# RegisterMemAddr.net
KiCad netlist of a schematic drawn in Altium Designer
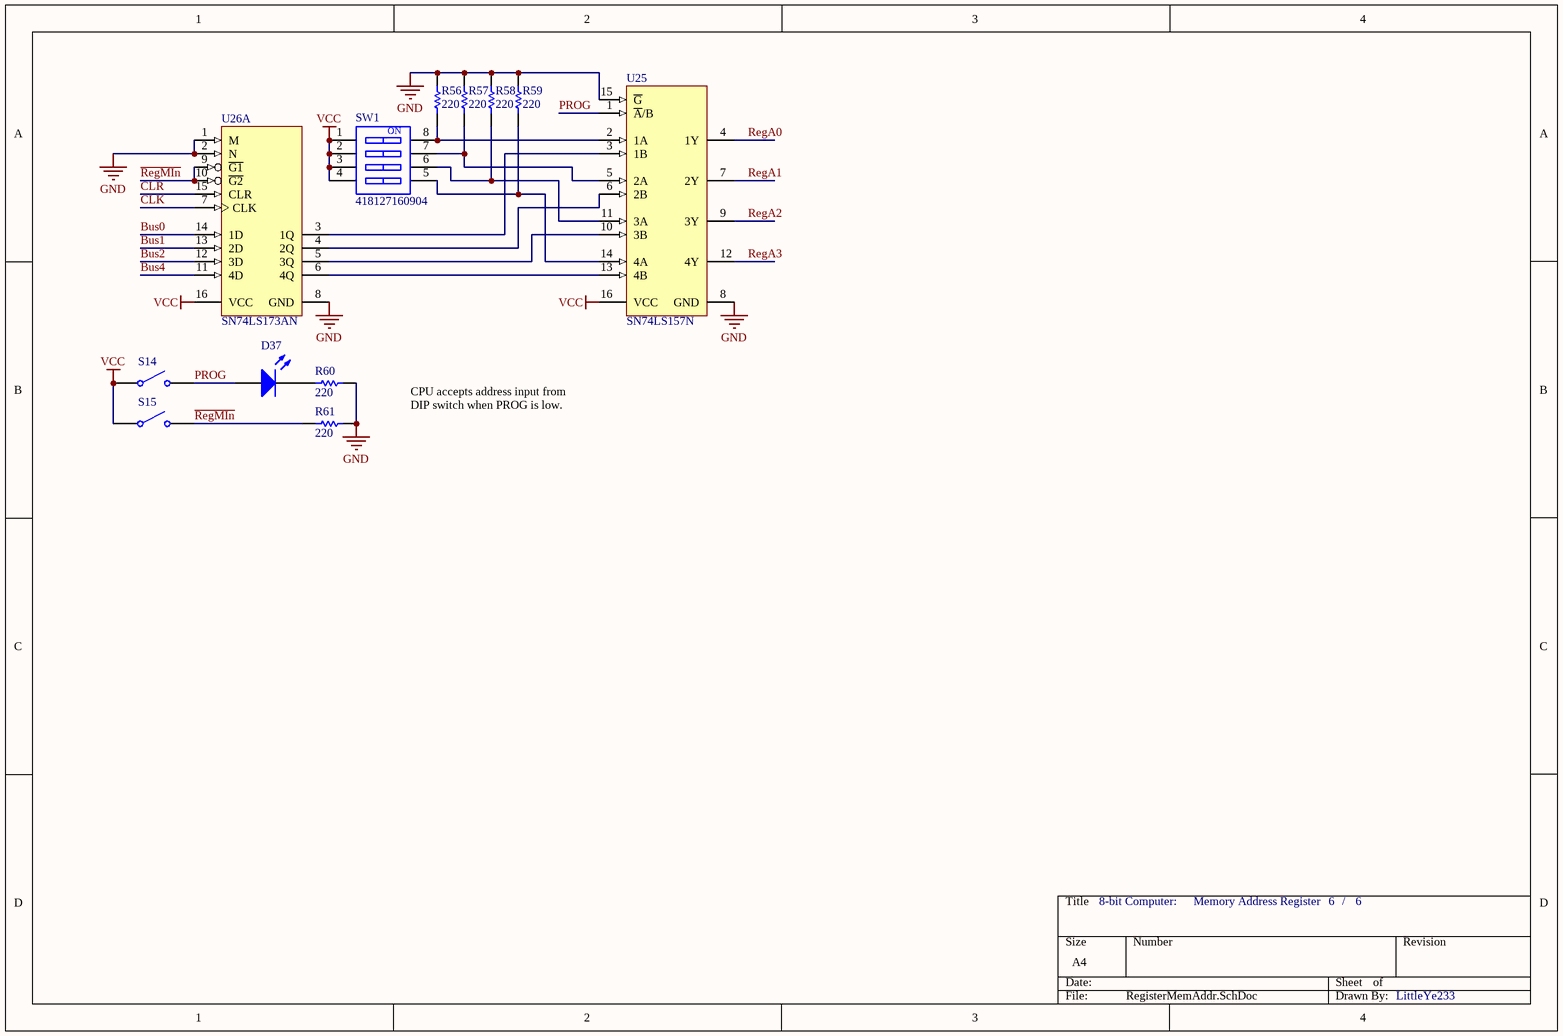
[diagram p0: RegisterMemAddr.SchDoc]

(export (version "E")
  (design (tool "Eeschema 10.0.6"))
  (components
    (comp (ref "D37")
      (value "Light-Emitting Diode")
      (libsource (lib "Simulation Generic Components") (part "LED"))
    )
    (comp (ref "R56")
      (value "220")
      (description "Resistor")
      (libsource (lib "Simulation Generic Components") (part "Resistor"))
    )
    (comp (ref "R57")
      (value "220")
      (description "Resistor")
      (libsource (lib "Simulation Generic Components") (part "Resistor"))
    )
    (comp (ref "R58")
      (value "220")
      (description "Resistor")
      (libsource (lib "Simulation Generic Components") (part "Resistor"))
    )
    (comp (ref "R59")
      (value "220")
      (description "Resistor")
      (libsource (lib "Simulation Generic Components") (part "Resistor"))
    )
    (comp (ref "R60")
      (value "220")
      (description "Resistor")
      (libsource (lib "Simulation Generic Components") (part "Resistor"))
    )
    (comp (ref "R61")
      (value "220")
      (description "Resistor")
      (libsource (lib "Simulation Generic Components") (part "Resistor"))
    )
    (comp (ref "S14")
      (value "Single-Pole, Single-Throw Switch")
      (libsource (lib "Simulation Generic Components") (part "SPST SW"))
    )
    (comp (ref "S15")
      (value "Single-Pole, Single-Throw Switch")
      (libsource (lib "Simulation Generic Components") (part "SPST SW"))
    )
    (comp (ref "SW1")
      (value "418127160904")
      (footprint "418127160904")
      (libsource (lib "418127160904") (part "CMP-1439-00004-2"))
    )
    (comp (ref "U25")
      (value "SN74LS157N")
      (footprint "N0016A")
      (description "Quadruple 2-Line To 1-Line Data Selectors/Multiplexers, N0016A, TUBE")
      (fields
        (field (name "MANUFACTURER") "Texas Instruments")
        (field (name "GENERIC PART NUMBER") "SN74LS157")
      )
      (libsource (lib "SN74LS157N") (part "CMP-1633-00683-2"))
    )
    (comp (ref "U26")
      (value "SN74LS173AN")
      (footprint "N0016A")
      (description "4-Bit D-type Registers with 3-State Outputs, N0016A, TUBE")
      (fields
        (field (name "MANUFACTURER") "Texas Instruments")
        (field (name "GENERIC PART NUMBER") "SN74LS173A")
      )
      (libsource (lib "SN74LS173AN") (part "CMP-1619-00777-2"))
    )
  )
  (nets
    (net (code "1") (name "/Bus0") (class "Default")
      (node (ref "U26") (pin "14") (pinfunction "1D_14") (pintype "input"))
    )
    (net (code "2") (name "/Bus1") (class "Default")
      (node (ref "U26") (pin "13") (pinfunction "2D_13") (pintype "input"))
    )
    (net (code "3") (name "/Bus2") (class "Default")
      (node (ref "U26") (pin "12") (pinfunction "3D_12") (pintype "input"))
    )
    (net (code "4") (name "/Bus4") (class "Default")
      (node (ref "U26") (pin "11") (pinfunction "4D_11") (pintype "input"))
    )
    (net (code "5") (name "/CLK") (class "Default")
      (node (ref "U26") (pin "7") (pinfunction "CLK_7") (pintype "input"))
    )
    (net (code "6") (name "/CLR") (class "Default")
      (node (ref "U26") (pin "15") (pinfunction "CLR_15") (pintype "input"))
    )
    (net (code "7") (name "/PROG") (class "Default")
      (node (ref "D37") (pin "1") (pinfunction "A_1") (pintype "passive"))
      (node (ref "S14") (pin "2") (pinfunction "2_2") (pintype "passive"))
      (node (ref "U25") (pin "1") (pinfunction "~{A}/B_1") (pintype "input"))
    )
    (net (code "8") (name "/RegA0") (class "Default")
      (node (ref "U25") (pin "4") (pinfunction "1Y_4") (pintype "passive"))
    )
    (net (code "9") (name "/RegA1") (class "Default")
      (node (ref "U25") (pin "7") (pinfunction "2Y_7") (pintype "passive"))
    )
    (net (code "10") (name "/RegA2") (class "Default")
      (node (ref "U25") (pin "9") (pinfunction "3Y_9") (pintype "passive"))
    )
    (net (code "11") (name "/RegA3") (class "Default")
      (node (ref "U25") (pin "12") (pinfunction "4Y_12") (pintype "passive"))
    )
    (net (code "12") (name "/~{RegMIn}") (class "Default")
      (node (ref "R61") (pin "2") (pinfunction "2_2") (pintype "passive"))
      (node (ref "S15") (pin "2") (pinfunction "2_2") (pintype "passive"))
      (node (ref "U26") (pin "10") (pinfunction "~{G2}_10") (pintype "input"))
      (node (ref "U26") (pin "9") (pinfunction "~{G1}_9") (pintype "input"))
    )
    (net (code "13") (name "GND") (class "Default")
      (node (ref "R56") (pin "2") (pinfunction "2_2") (pintype "passive"))
      (node (ref "R57") (pin "2") (pinfunction "2_2") (pintype "passive"))
      (node (ref "R58") (pin "2") (pinfunction "2_2") (pintype "passive"))
      (node (ref "R59") (pin "2") (pinfunction "2_2") (pintype "passive"))
      (node (ref "R60") (pin "1") (pinfunction "1_1") (pintype "passive"))
      (node (ref "R61") (pin "1") (pinfunction "1_1") (pintype "passive"))
      (node (ref "U25") (pin "15") (pinfunction "~{G}_15") (pintype "input"))
      (node (ref "U25") (pin "8") (pinfunction "GND_8") (pintype "power_in"))
      (node (ref "U26") (pin "1") (pinfunction "M_1") (pintype "input"))
      (node (ref "U26") (pin "2") (pinfunction "N_2") (pintype "input"))
      (node (ref "U26") (pin "8") (pinfunction "GND_8") (pintype "power_in"))
    )
    (net (code "14") (name "Net-(D37-K)") (class "Default")
      (node (ref "D37") (pin "2") (pinfunction "K_2") (pintype "passive"))
      (node (ref "R60") (pin "2") (pinfunction "2_2") (pintype "passive"))
    )
    (net (code "15") (name "Net-(U25-1A)") (class "Default")
      (node (ref "R56") (pin "1") (pinfunction "1_1") (pintype "passive"))
      (node (ref "SW1") (pin "8") (pinfunction "8_8") (pintype "passive"))
      (node (ref "U25") (pin "2") (pinfunction "1A_2") (pintype "input"))
    )
    (net (code "16") (name "Net-(U25-1B)") (class "Default")
      (node (ref "U25") (pin "3") (pinfunction "1B_3") (pintype "input"))
      (node (ref "U26") (pin "3") (pinfunction "1Q_3") (pintype "tri_state"))
    )
    (net (code "17") (name "Net-(U25-2A)") (class "Default")
      (node (ref "R57") (pin "1") (pinfunction "1_1") (pintype "passive"))
      (node (ref "SW1") (pin "7") (pinfunction "7_7") (pintype "passive"))
      (node (ref "U25") (pin "5") (pinfunction "2A_5") (pintype "input"))
    )
    (net (code "18") (name "Net-(U25-2B)") (class "Default")
      (node (ref "U25") (pin "6") (pinfunction "2B_6") (pintype "input"))
      (node (ref "U26") (pin "4") (pinfunction "2Q_4") (pintype "tri_state"))
    )
    (net (code "19") (name "Net-(U25-3A)") (class "Default")
      (node (ref "R58") (pin "1") (pinfunction "1_1") (pintype "passive"))
      (node (ref "SW1") (pin "6") (pinfunction "6_6") (pintype "passive"))
      (node (ref "U25") (pin "11") (pinfunction "3A_11") (pintype "input"))
    )
    (net (code "20") (name "Net-(U25-3B)") (class "Default")
      (node (ref "U25") (pin "10") (pinfunction "3B_10") (pintype "input"))
      (node (ref "U26") (pin "5") (pinfunction "3Q_5") (pintype "tri_state"))
    )
    (net (code "21") (name "Net-(U25-4A)") (class "Default")
      (node (ref "R59") (pin "1") (pinfunction "1_1") (pintype "passive"))
      (node (ref "SW1") (pin "5") (pinfunction "5_5") (pintype "passive"))
      (node (ref "U25") (pin "14") (pinfunction "4A_14") (pintype "input"))
    )
    (net (code "22") (name "Net-(U25-4B)") (class "Default")
      (node (ref "U25") (pin "13") (pinfunction "4B_13") (pintype "input"))
      (node (ref "U26") (pin "6") (pinfunction "4Q_6") (pintype "tri_state"))
    )
    (net (code "23") (name "VCC") (class "Default")
      (node (ref "S14") (pin "1") (pinfunction "1_1") (pintype "passive"))
      (node (ref "S15") (pin "1") (pinfunction "1_1") (pintype "passive"))
      (node (ref "SW1") (pin "1") (pinfunction "1_1") (pintype "passive"))
      (node (ref "SW1") (pin "2") (pinfunction "2_2") (pintype "passive"))
      (node (ref "SW1") (pin "3") (pinfunction "3_3") (pintype "passive"))
      (node (ref "SW1") (pin "4") (pinfunction "4_4") (pintype "passive"))
      (node (ref "U25") (pin "16") (pinfunction "VCC_16") (pintype "power_in"))
      (node (ref "U26") (pin "16") (pinfunction "VCC_16") (pintype "power_in"))
    )
  )
)
